# untitled.net
KiCad netlist of a schematic drawn in EAGLE
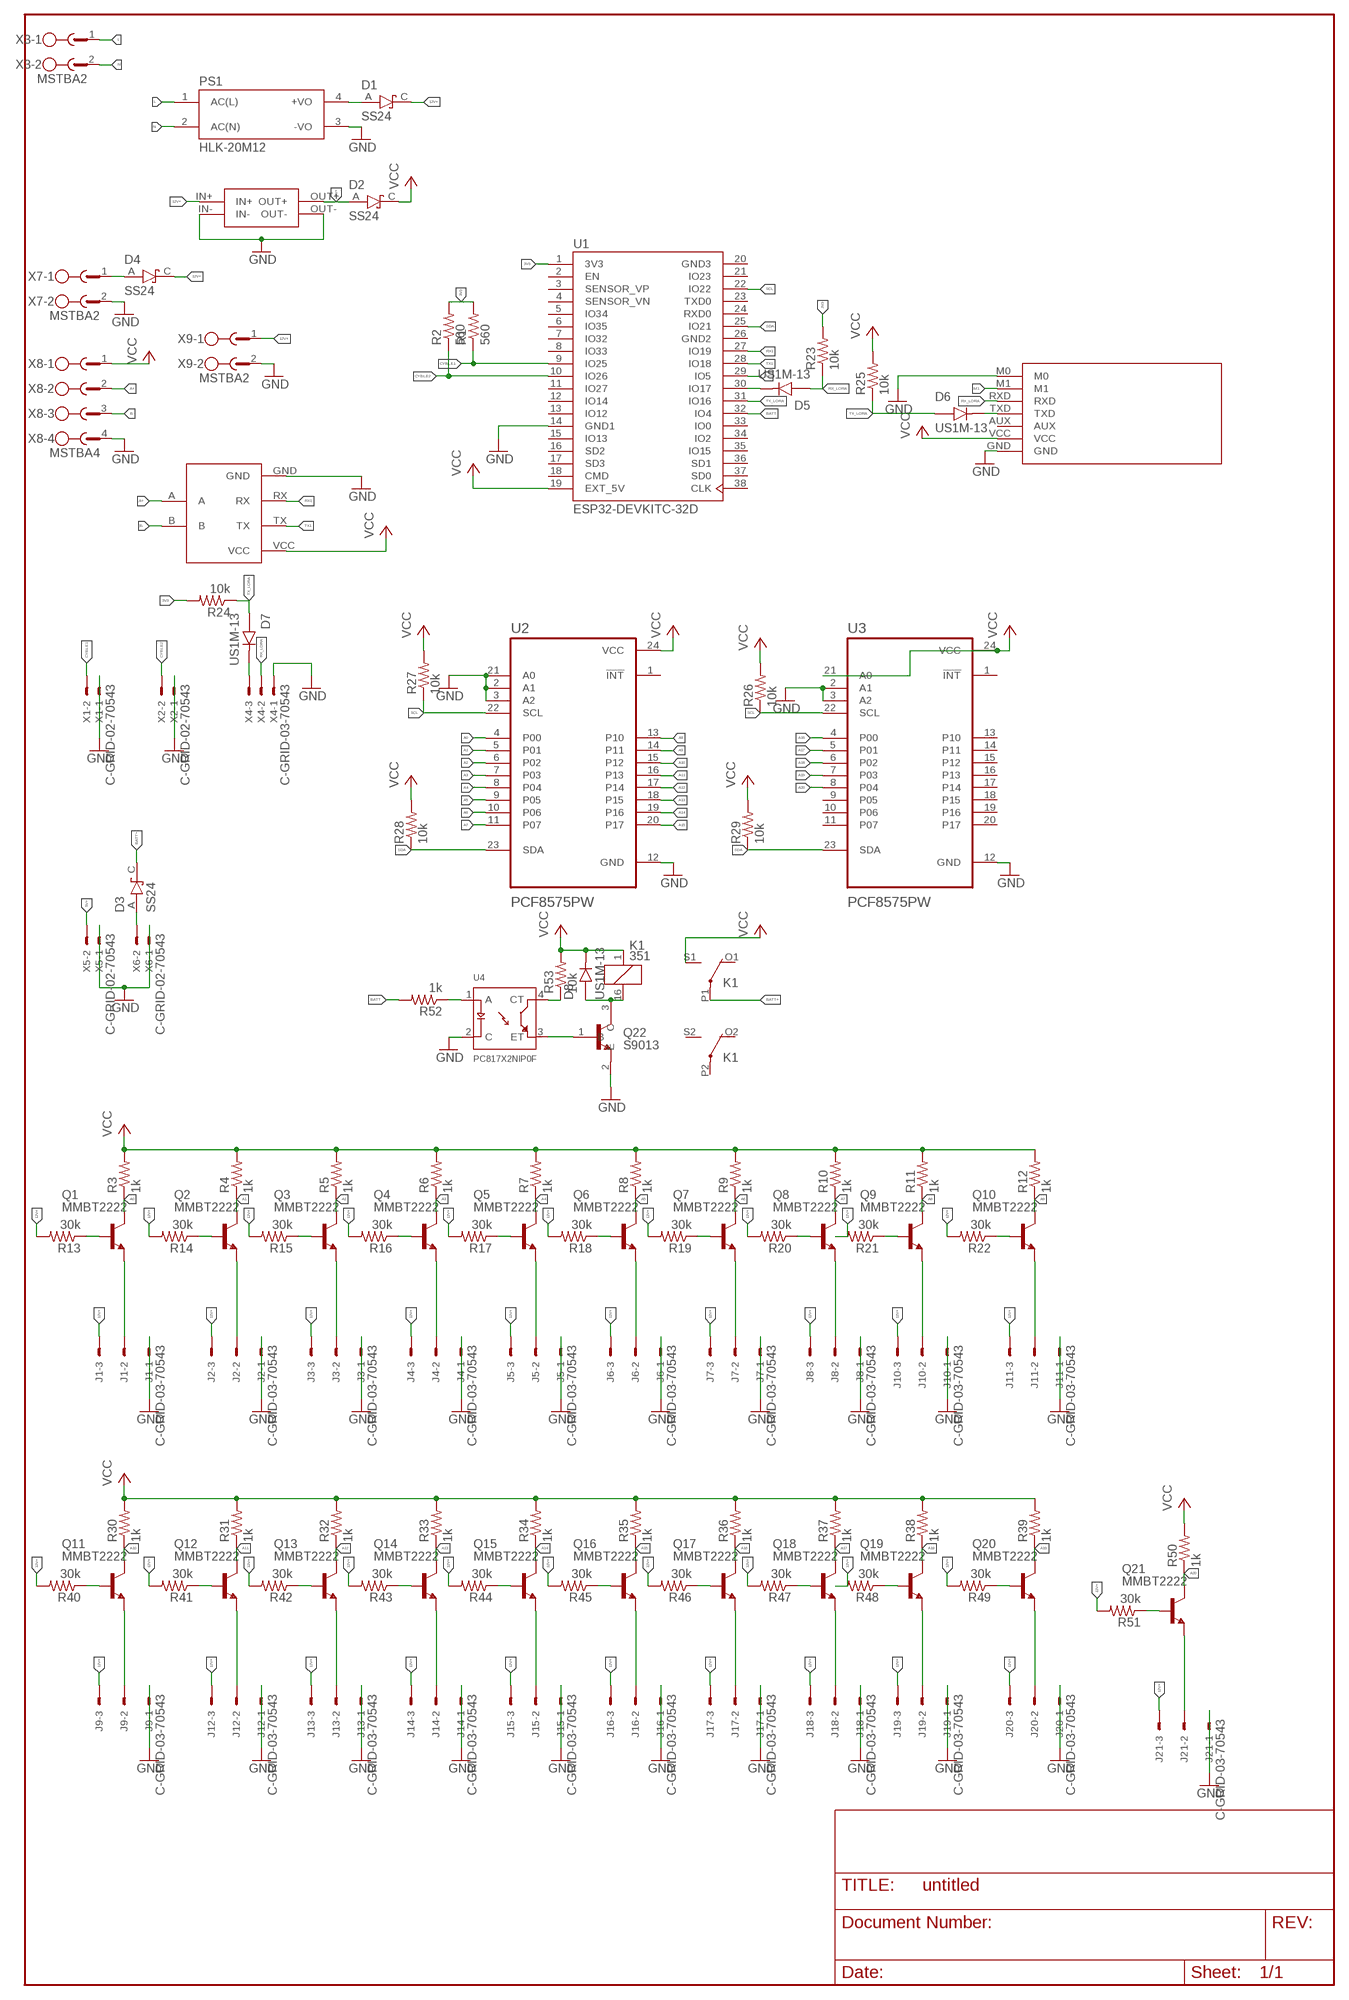
[diagram p0: schematic, sheet 1]

(export (version "E")
  (design (tool "Eeschema 10.0.6"))
  (components
    (comp (ref "D1")
      (value "SS24")
      (footprint "eagle-import:DIOM5336X265N")
      (fields (field (name "MF") "ON Semiconductor"))
      (libsource (lib "eagle-import") (part "SS24"))
    )
    (comp (ref "D2")
      (value "SS24")
      (footprint "eagle-import:DIOM5336X265N")
      (fields (field (name "MF") "ON Semiconductor"))
      (libsource (lib "eagle-import") (part "SS24"))
    )
    (comp (ref "D3")
      (value "SS24")
      (footprint "eagle-import:DIOM5336X265N")
      (fields (field (name "MF") "ON Semiconductor"))
      (libsource (lib "eagle-import") (part "SS24"))
    )
    (comp (ref "D4")
      (value "SS24")
      (footprint "eagle-import:DIOM5336X265N")
      (fields (field (name "MF") "ON Semiconductor"))
      (libsource (lib "eagle-import") (part "SS24"))
    )
    (comp (ref "D5")
      (value "US1M-13")
      (footprint "eagle-import:DIOM5226X240N")
      (fields (field (name "MF") "Diodes Incorporated"))
      (libsource (lib "eagle-import") (part "US1M-13"))
    )
    (comp (ref "D6")
      (value "US1M-13")
      (footprint "eagle-import:DIOM5226X240N")
      (fields (field (name "MF") "Diodes Incorporated"))
      (libsource (lib "eagle-import") (part "US1M-13"))
    )
    (comp (ref "D7")
      (value "US1M-13")
      (footprint "eagle-import:DIOM5226X240N")
      (fields (field (name "MF") "Diodes Incorporated"))
      (libsource (lib "eagle-import") (part "US1M-13"))
    )
    (comp (ref "D8")
      (value "US1M-13")
      (footprint "eagle-import:DIOM5226X240N")
      (fields (field (name "MF") "Diodes Incorporated"))
      (libsource (lib "eagle-import") (part "US1M-13"))
    )
    (comp (ref "EBYTEE220-900T22D1")
      (value "EBYTEE220-900T22D")
      (footprint "eagle-import:EBYTEE220-900T22D")
      (libsource (lib "eagle-import") (part "EBYTEE220-900T22D"))
    )
    (comp (ref "J1")
      (value "C-GRID-03-70543")
      (footprint "eagle-import:70543-03")
      (fields (field (name "MF") "MOLEX"))
      (libsource (lib "eagle-import") (part "C-GRID-03-70543"))
    )
    (comp (ref "J2")
      (value "C-GRID-03-70543")
      (footprint "eagle-import:70543-03")
      (fields (field (name "MF") "MOLEX"))
      (libsource (lib "eagle-import") (part "C-GRID-03-70543"))
    )
    (comp (ref "J3")
      (value "C-GRID-03-70543")
      (footprint "eagle-import:70543-03")
      (fields (field (name "MF") "MOLEX"))
      (libsource (lib "eagle-import") (part "C-GRID-03-70543"))
    )
    (comp (ref "J4")
      (value "C-GRID-03-70543")
      (footprint "eagle-import:70543-03")
      (fields (field (name "MF") "MOLEX"))
      (libsource (lib "eagle-import") (part "C-GRID-03-70543"))
    )
    (comp (ref "J5")
      (value "C-GRID-03-70543")
      (footprint "eagle-import:70543-03")
      (fields (field (name "MF") "MOLEX"))
      (libsource (lib "eagle-import") (part "C-GRID-03-70543"))
    )
    (comp (ref "J6")
      (value "C-GRID-03-70543")
      (footprint "eagle-import:70543-03")
      (fields (field (name "MF") "MOLEX"))
      (libsource (lib "eagle-import") (part "C-GRID-03-70543"))
    )
    (comp (ref "J7")
      (value "C-GRID-03-70543")
      (footprint "eagle-import:70543-03")
      (fields (field (name "MF") "MOLEX"))
      (libsource (lib "eagle-import") (part "C-GRID-03-70543"))
    )
    (comp (ref "J8")
      (value "C-GRID-03-70543")
      (footprint "eagle-import:70543-03")
      (fields (field (name "MF") "MOLEX"))
      (libsource (lib "eagle-import") (part "C-GRID-03-70543"))
    )
    (comp (ref "J9")
      (value "C-GRID-03-70543")
      (footprint "eagle-import:70543-03")
      (fields (field (name "MF") "MOLEX"))
      (libsource (lib "eagle-import") (part "C-GRID-03-70543"))
    )
    (comp (ref "J10")
      (value "C-GRID-03-70543")
      (footprint "eagle-import:70543-03")
      (fields (field (name "MF") "MOLEX"))
      (libsource (lib "eagle-import") (part "C-GRID-03-70543"))
    )
    (comp (ref "J11")
      (value "C-GRID-03-70543")
      (footprint "eagle-import:70543-03")
      (fields (field (name "MF") "MOLEX"))
      (libsource (lib "eagle-import") (part "C-GRID-03-70543"))
    )
    (comp (ref "J12")
      (value "C-GRID-03-70543")
      (footprint "eagle-import:70543-03")
      (fields (field (name "MF") "MOLEX"))
      (libsource (lib "eagle-import") (part "C-GRID-03-70543"))
    )
    (comp (ref "J13")
      (value "C-GRID-03-70543")
      (footprint "eagle-import:70543-03")
      (fields (field (name "MF") "MOLEX"))
      (libsource (lib "eagle-import") (part "C-GRID-03-70543"))
    )
    (comp (ref "J14")
      (value "C-GRID-03-70543")
      (footprint "eagle-import:70543-03")
      (fields (field (name "MF") "MOLEX"))
      (libsource (lib "eagle-import") (part "C-GRID-03-70543"))
    )
    (comp (ref "J15")
      (value "C-GRID-03-70543")
      (footprint "eagle-import:70543-03")
      (fields (field (name "MF") "MOLEX"))
      (libsource (lib "eagle-import") (part "C-GRID-03-70543"))
    )
    (comp (ref "J16")
      (value "C-GRID-03-70543")
      (footprint "eagle-import:70543-03")
      (fields (field (name "MF") "MOLEX"))
      (libsource (lib "eagle-import") (part "C-GRID-03-70543"))
    )
    (comp (ref "J17")
      (value "C-GRID-03-70543")
      (footprint "eagle-import:70543-03")
      (fields (field (name "MF") "MOLEX"))
      (libsource (lib "eagle-import") (part "C-GRID-03-70543"))
    )
    (comp (ref "J18")
      (value "C-GRID-03-70543")
      (footprint "eagle-import:70543-03")
      (fields (field (name "MF") "MOLEX"))
      (libsource (lib "eagle-import") (part "C-GRID-03-70543"))
    )
    (comp (ref "J19")
      (value "C-GRID-03-70543")
      (footprint "eagle-import:70543-03")
      (fields (field (name "MF") "MOLEX"))
      (libsource (lib "eagle-import") (part "C-GRID-03-70543"))
    )
    (comp (ref "J20")
      (value "C-GRID-03-70543")
      (footprint "eagle-import:70543-03")
      (fields (field (name "MF") "MOLEX"))
      (libsource (lib "eagle-import") (part "C-GRID-03-70543"))
    )
    (comp (ref "J21")
      (value "C-GRID-03-70543")
      (footprint "eagle-import:70543-03")
      (fields (field (name "MF") "MOLEX"))
      (libsource (lib "eagle-import") (part "C-GRID-03-70543"))
    )
    (comp (ref "K1")
      (value "351")
      (footprint "eagle-import:351")
      (libsource (lib "eagle-import") (part "351"))
    )
    (comp (ref "MINI1")
      (value "MINI560")
      (footprint "eagle-import:MINI560")
      (libsource (lib "eagle-import") (part "MINI560"))
    )
    (comp (ref "PS1")
      (value "HLK-20M12")
      (footprint "eagle-import:CONV_HLK-20M12")
      (fields (field (name "MF") "Hi-link"))
      (libsource (lib "eagle-import") (part "HLK-20M12"))
    )
    (comp (ref "Q1")
      (value "MMBT2222")
      (footprint "eagle-import:SOT23-BEC")
      (fields (field (name "MF") "ON Semiconductor"))
      (libsource (lib "eagle-import") (part "MMBT2222"))
    )
    (comp (ref "Q2")
      (value "MMBT2222")
      (footprint "eagle-import:SOT23-BEC")
      (fields (field (name "MF") "ON Semiconductor"))
      (libsource (lib "eagle-import") (part "MMBT2222"))
    )
    (comp (ref "Q3")
      (value "MMBT2222")
      (footprint "eagle-import:SOT23-BEC")
      (fields (field (name "MF") "ON Semiconductor"))
      (libsource (lib "eagle-import") (part "MMBT2222"))
    )
    (comp (ref "Q4")
      (value "MMBT2222")
      (footprint "eagle-import:SOT23-BEC")
      (fields (field (name "MF") "ON Semiconductor"))
      (libsource (lib "eagle-import") (part "MMBT2222"))
    )
    (comp (ref "Q5")
      (value "MMBT2222")
      (footprint "eagle-import:SOT23-BEC")
      (fields (field (name "MF") "ON Semiconductor"))
      (libsource (lib "eagle-import") (part "MMBT2222"))
    )
    (comp (ref "Q6")
      (value "MMBT2222")
      (footprint "eagle-import:SOT23-BEC")
      (fields (field (name "MF") "ON Semiconductor"))
      (libsource (lib "eagle-import") (part "MMBT2222"))
    )
    (comp (ref "Q7")
      (value "MMBT2222")
      (footprint "eagle-import:SOT23-BEC")
      (fields (field (name "MF") "ON Semiconductor"))
      (libsource (lib "eagle-import") (part "MMBT2222"))
    )
    (comp (ref "Q8")
      (value "MMBT2222")
      (footprint "eagle-import:SOT23-BEC")
      (fields (field (name "MF") "ON Semiconductor"))
      (libsource (lib "eagle-import") (part "MMBT2222"))
    )
    (comp (ref "Q9")
      (value "MMBT2222")
      (footprint "eagle-import:SOT23-BEC")
      (fields (field (name "MF") "ON Semiconductor"))
      (libsource (lib "eagle-import") (part "MMBT2222"))
    )
    (comp (ref "Q10")
      (value "MMBT2222")
      (footprint "eagle-import:SOT23-BEC")
      (fields (field (name "MF") "ON Semiconductor"))
      (libsource (lib "eagle-import") (part "MMBT2222"))
    )
    (comp (ref "Q11")
      (value "MMBT2222")
      (footprint "eagle-import:SOT23-BEC")
      (fields (field (name "MF") "ON Semiconductor"))
      (libsource (lib "eagle-import") (part "MMBT2222"))
    )
    (comp (ref "Q12")
      (value "MMBT2222")
      (footprint "eagle-import:SOT23-BEC")
      (fields (field (name "MF") "ON Semiconductor"))
      (libsource (lib "eagle-import") (part "MMBT2222"))
    )
    (comp (ref "Q13")
      (value "MMBT2222")
      (footprint "eagle-import:SOT23-BEC")
      (fields (field (name "MF") "ON Semiconductor"))
      (libsource (lib "eagle-import") (part "MMBT2222"))
    )
    (comp (ref "Q14")
      (value "MMBT2222")
      (footprint "eagle-import:SOT23-BEC")
      (fields (field (name "MF") "ON Semiconductor"))
      (libsource (lib "eagle-import") (part "MMBT2222"))
    )
    (comp (ref "Q15")
      (value "MMBT2222")
      (footprint "eagle-import:SOT23-BEC")
      (fields (field (name "MF") "ON Semiconductor"))
      (libsource (lib "eagle-import") (part "MMBT2222"))
    )
    (comp (ref "Q16")
      (value "MMBT2222")
      (footprint "eagle-import:SOT23-BEC")
      (fields (field (name "MF") "ON Semiconductor"))
      (libsource (lib "eagle-import") (part "MMBT2222"))
    )
    (comp (ref "Q17")
      (value "MMBT2222")
      (footprint "eagle-import:SOT23-BEC")
      (fields (field (name "MF") "ON Semiconductor"))
      (libsource (lib "eagle-import") (part "MMBT2222"))
    )
    (comp (ref "Q18")
      (value "MMBT2222")
      (footprint "eagle-import:SOT23-BEC")
      (fields (field (name "MF") "ON Semiconductor"))
      (libsource (lib "eagle-import") (part "MMBT2222"))
    )
    (comp (ref "Q19")
      (value "MMBT2222")
      (footprint "eagle-import:SOT23-BEC")
      (fields (field (name "MF") "ON Semiconductor"))
      (libsource (lib "eagle-import") (part "MMBT2222"))
    )
    (comp (ref "Q20")
      (value "MMBT2222")
      (footprint "eagle-import:SOT23-BEC")
      (fields (field (name "MF") "ON Semiconductor"))
      (libsource (lib "eagle-import") (part "MMBT2222"))
    )
    (comp (ref "Q21")
      (value "MMBT2222")
      (footprint "eagle-import:SOT23-BEC")
      (fields (field (name "MF") "ON Semiconductor"))
      (libsource (lib "eagle-import") (part "MMBT2222"))
    )
    (comp (ref "Q22")
      (value "S9013")
      (footprint "eagle-import:SOT95P240X120-3N")
      (fields (field (name "MF") "JCET"))
      (libsource (lib "eagle-import") (part "S9013"))
    )
    (comp (ref "R1")
      (value "560")
      (footprint "eagle-import:M0805")
      (libsource (lib "eagle-import") (part "R-US_M0805"))
    )
    (comp (ref "R2")
      (value "560")
      (footprint "eagle-import:M0805")
      (libsource (lib "eagle-import") (part "R-US_M0805"))
    )
    (comp (ref "R3")
      (value "1k")
      (footprint "eagle-import:M0805")
      (libsource (lib "eagle-import") (part "R-US_M0805"))
    )
    (comp (ref "R4")
      (value "1k")
      (footprint "eagle-import:M0805")
      (libsource (lib "eagle-import") (part "R-US_M0805"))
    )
    (comp (ref "R5")
      (value "1k")
      (footprint "eagle-import:M0805")
      (libsource (lib "eagle-import") (part "R-US_M0805"))
    )
    (comp (ref "R6")
      (value "1k")
      (footprint "eagle-import:M0805")
      (libsource (lib "eagle-import") (part "R-US_M0805"))
    )
    (comp (ref "R7")
      (value "1k")
      (footprint "eagle-import:M0805")
      (libsource (lib "eagle-import") (part "R-US_M0805"))
    )
    (comp (ref "R8")
      (value "1k")
      (footprint "eagle-import:M0805")
      (libsource (lib "eagle-import") (part "R-US_M0805"))
    )
    (comp (ref "R9")
      (value "1k")
      (footprint "eagle-import:M0805")
      (libsource (lib "eagle-import") (part "R-US_M0805"))
    )
    (comp (ref "R10")
      (value "1k")
      (footprint "eagle-import:M0805")
      (libsource (lib "eagle-import") (part "R-US_M0805"))
    )
    (comp (ref "R11")
      (value "1k")
      (footprint "eagle-import:M0805")
      (libsource (lib "eagle-import") (part "R-US_M0805"))
    )
    (comp (ref "R12")
      (value "1k")
      (footprint "eagle-import:M0805")
      (libsource (lib "eagle-import") (part "R-US_M0805"))
    )
    (comp (ref "R13")
      (value "30k")
      (footprint "eagle-import:M0805")
      (libsource (lib "eagle-import") (part "R-US_M0805"))
    )
    (comp (ref "R14")
      (value "30k")
      (footprint "eagle-import:M0805")
      (libsource (lib "eagle-import") (part "R-US_M0805"))
    )
    (comp (ref "R15")
      (value "30k")
      (footprint "eagle-import:M0805")
      (libsource (lib "eagle-import") (part "R-US_M0805"))
    )
    (comp (ref "R16")
      (value "30k")
      (footprint "eagle-import:M0805")
      (libsource (lib "eagle-import") (part "R-US_M0805"))
    )
    (comp (ref "R17")
      (value "30k")
      (footprint "eagle-import:M0805")
      (libsource (lib "eagle-import") (part "R-US_M0805"))
    )
    (comp (ref "R18")
      (value "30k")
      (footprint "eagle-import:M0805")
      (libsource (lib "eagle-import") (part "R-US_M0805"))
    )
    (comp (ref "R19")
      (value "30k")
      (footprint "eagle-import:M0805")
      (libsource (lib "eagle-import") (part "R-US_M0805"))
    )
    (comp (ref "R20")
      (value "30k")
      (footprint "eagle-import:M0805")
      (libsource (lib "eagle-import") (part "R-US_M0805"))
    )
    (comp (ref "R21")
      (value "30k")
      (footprint "eagle-import:M0805")
      (libsource (lib "eagle-import") (part "R-US_M0805"))
    )
    (comp (ref "R22")
      (value "30k")
      (footprint "eagle-import:M0805")
      (libsource (lib "eagle-import") (part "R-US_M0805"))
    )
    (comp (ref "R23")
      (value "10k")
      (footprint "eagle-import:M0805")
      (libsource (lib "eagle-import") (part "R-US_M0805"))
    )
    (comp (ref "R24")
      (value "10k")
      (footprint "eagle-import:M0805")
      (libsource (lib "eagle-import") (part "R-US_M0805"))
    )
    (comp (ref "R25")
      (value "10k")
      (footprint "eagle-import:M0805")
      (libsource (lib "eagle-import") (part "R-US_M0805"))
    )
    (comp (ref "R26")
      (value "10k")
      (footprint "eagle-import:M0805")
      (libsource (lib "eagle-import") (part "R-US_M0805"))
    )
    (comp (ref "R27")
      (value "10k")
      (footprint "eagle-import:M0805")
      (libsource (lib "eagle-import") (part "R-US_M0805"))
    )
    (comp (ref "R28")
      (value "10k")
      (footprint "eagle-import:M0805")
      (libsource (lib "eagle-import") (part "R-US_M0805"))
    )
    (comp (ref "R29")
      (value "10k")
      (footprint "eagle-import:M0805")
      (libsource (lib "eagle-import") (part "R-US_M0805"))
    )
    (comp (ref "R30")
      (value "1k")
      (footprint "eagle-import:M0805")
      (libsource (lib "eagle-import") (part "R-US_M0805"))
    )
    (comp (ref "R31")
      (value "1k")
      (footprint "eagle-import:M0805")
      (libsource (lib "eagle-import") (part "R-US_M0805"))
    )
    (comp (ref "R32")
      (value "1k")
      (footprint "eagle-import:M0805")
      (libsource (lib "eagle-import") (part "R-US_M0805"))
    )
    (comp (ref "R33")
      (value "1k")
      (footprint "eagle-import:M0805")
      (libsource (lib "eagle-import") (part "R-US_M0805"))
    )
    (comp (ref "R34")
      (value "1k")
      (footprint "eagle-import:M0805")
      (libsource (lib "eagle-import") (part "R-US_M0805"))
    )
    (comp (ref "R35")
      (value "1k")
      (footprint "eagle-import:M0805")
      (libsource (lib "eagle-import") (part "R-US_M0805"))
    )
    (comp (ref "R36")
      (value "1k")
      (footprint "eagle-import:M0805")
      (libsource (lib "eagle-import") (part "R-US_M0805"))
    )
    (comp (ref "R37")
      (value "1k")
      (footprint "eagle-import:M0805")
      (libsource (lib "eagle-import") (part "R-US_M0805"))
    )
    (comp (ref "R38")
      (value "1k")
      (footprint "eagle-import:M0805")
      (libsource (lib "eagle-import") (part "R-US_M0805"))
    )
    (comp (ref "R39")
      (value "1k")
      (footprint "eagle-import:M0805")
      (libsource (lib "eagle-import") (part "R-US_M0805"))
    )
    (comp (ref "R40")
      (value "30k")
      (footprint "eagle-import:M0805")
      (libsource (lib "eagle-import") (part "R-US_M0805"))
    )
    (comp (ref "R41")
      (value "30k")
      (footprint "eagle-import:M0805")
      (libsource (lib "eagle-import") (part "R-US_M0805"))
    )
    (comp (ref "R42")
      (value "30k")
      (footprint "eagle-import:M0805")
      (libsource (lib "eagle-import") (part "R-US_M0805"))
    )
    (comp (ref "R43")
      (value "30k")
      (footprint "eagle-import:M0805")
      (libsource (lib "eagle-import") (part "R-US_M0805"))
    )
    (comp (ref "R44")
      (value "30k")
      (footprint "eagle-import:M0805")
      (libsource (lib "eagle-import") (part "R-US_M0805"))
    )
    (comp (ref "R45")
      (value "30k")
      (footprint "eagle-import:M0805")
      (libsource (lib "eagle-import") (part "R-US_M0805"))
    )
    (comp (ref "R46")
      (value "30k")
      (footprint "eagle-import:M0805")
      (libsource (lib "eagle-import") (part "R-US_M0805"))
    )
    (comp (ref "R47")
      (value "30k")
      (footprint "eagle-import:M0805")
      (libsource (lib "eagle-import") (part "R-US_M0805"))
    )
    (comp (ref "R48")
      (value "30k")
      (footprint "eagle-import:M0805")
      (libsource (lib "eagle-import") (part "R-US_M0805"))
    )
    (comp (ref "R49")
      (value "30k")
      (footprint "eagle-import:M0805")
      (libsource (lib "eagle-import") (part "R-US_M0805"))
    )
    (comp (ref "R50")
      (value "1k")
      (footprint "eagle-import:M0805")
      (libsource (lib "eagle-import") (part "R-US_M0805"))
    )
    (comp (ref "R51")
      (value "30k")
      (footprint "eagle-import:M0805")
      (libsource (lib "eagle-import") (part "R-US_M0805"))
    )
    (comp (ref "R52")
      (value "1k")
      (footprint "eagle-import:M0805")
      (libsource (lib "eagle-import") (part "R-US_M0805"))
    )
    (comp (ref "R53")
      (value "10k")
      (footprint "eagle-import:M0805")
      (libsource (lib "eagle-import") (part "R-US_M0805"))
    )
    (comp (ref "TTL-RS1")
      (value "TTL-RS485")
      (footprint "eagle-import:TTL-RS485")
      (libsource (lib "eagle-import") (part "TTL-RS485"))
    )
    (comp (ref "U1")
      (value "ESP32-DEVKITC-32D")
      (footprint "eagle-import:MODULE_ESP32-DEVKITC-32D")
      (fields (field (name "MF") "Espressif Systems"))
      (libsource (lib "eagle-import") (part "ESP32-DEVKITC-32D"))
    )
    (comp (ref "U2")
      (value "PCF8575PW")
      (footprint "eagle-import:SOP65P640X120-24N")
      (fields (field (name "MF") "Texas Instruments"))
      (libsource (lib "eagle-import") (part "PCF8575PW"))
    )
    (comp (ref "U3")
      (value "PCF8575PW")
      (footprint "eagle-import:SOP65P640X120-24N")
      (fields (field (name "MF") "Texas Instruments"))
      (libsource (lib "eagle-import") (part "PCF8575PW"))
    )
    (comp (ref "U4")
      (value "PC817X2NIP0F")
      (footprint "eagle-import:SOT254P975X400-4N")
      (fields (field (name "MF") "Sharp Microelectronics"))
      (libsource (lib "eagle-import") (part "PC817X2NIP0F"))
    )
    (comp (ref "X1")
      (value "C-GRID-02-70543")
      (footprint "eagle-import:70543-02")
      (fields (field (name "MF") "MOLEX"))
      (libsource (lib "eagle-import") (part "C-GRID-02-70543"))
    )
    (comp (ref "X2")
      (value "C-GRID-02-70543")
      (footprint "eagle-import:70543-02")
      (fields (field (name "MF") "MOLEX"))
      (libsource (lib "eagle-import") (part "C-GRID-02-70543"))
    )
    (comp (ref "X3")
      (value "MSTBA2")
      (footprint "eagle-import:MSTBA2")
      (fields (field (name "MF") "FARNELL") (field (name "MPN") "1757242"))
      (libsource (lib "eagle-import") (part "MSTBA2"))
    )
    (comp (ref "X4")
      (value "C-GRID-03-70543")
      (footprint "eagle-import:70543-03")
      (fields (field (name "MF") "MOLEX"))
      (libsource (lib "eagle-import") (part "C-GRID-03-70543"))
    )
    (comp (ref "X5")
      (value "C-GRID-02-70543")
      (footprint "eagle-import:70543-02")
      (fields (field (name "MF") "MOLEX"))
      (libsource (lib "eagle-import") (part "C-GRID-02-70543"))
    )
    (comp (ref "X6")
      (value "C-GRID-02-70543")
      (footprint "eagle-import:70543-02")
      (fields (field (name "MF") "MOLEX"))
      (libsource (lib "eagle-import") (part "C-GRID-02-70543"))
    )
    (comp (ref "X7")
      (value "MSTBA2")
      (footprint "eagle-import:MSTBA2")
      (fields (field (name "MF") "FARNELL") (field (name "MPN") "1757242"))
      (libsource (lib "eagle-import") (part "MSTBA2"))
    )
    (comp (ref "X8")
      (value "MSTBA4")
      (footprint "eagle-import:MSTBA4")
      (fields (field (name "MF") "FARNELL") (field (name "MPN") "1757268"))
      (libsource (lib "eagle-import") (part "MSTBA4"))
    )
    (comp (ref "X9")
      (value "MSTBA2")
      (footprint "eagle-import:MSTBA2")
      (fields (field (name "MF") "FARNELL") (field (name "MPN") "1757242"))
      (libsource (lib "eagle-import") (part "MSTBA2"))
    )
  )
  (nets
    (net (code "1") (name "/GND2") (class "Default")
      (node (ref "U1") (pin "26") (pinfunction "GND2_26") (pintype "power_in"))
    )
    (net (code "2") (name "/GND3") (class "Default")
      (node (ref "U1") (pin "20") (pinfunction "GND3_20") (pintype "power_in"))
    )
    (net (code "3") (name "3V3") (class "Default")
      (node (ref "R1") (pin "2") (pinfunction "2_2") (pintype "passive"))
      (node (ref "R2") (pin "2") (pinfunction "2_2") (pintype "passive"))
      (node (ref "R23") (pin "2") (pinfunction "2_2") (pintype "passive"))
      (node (ref "R24") (pin "2") (pinfunction "2_2") (pintype "passive"))
      (node (ref "U1") (pin "1") (pinfunction "3V3_1") (pintype "power_in"))
    )
    (net (code "4") (name "5V+") (class "Default")
      (node (ref "D2") (pin "A") (pinfunction "A_A") (pintype "passive"))
      (node (ref "MINI1") (pin "OUT+") (pinfunction "OUT+_OUT+") (pintype "bidirectional"))
      (node (ref "X5") (pin "2") (pinfunction "S_2") (pintype "passive"))
    )
    (net (code "5") (name "12V+") (class "Default")
      (node (ref "D1") (pin "C") (pinfunction "K_C") (pintype "passive"))
      (node (ref "D4") (pin "C") (pinfunction "K_C") (pintype "passive"))
      (node (ref "J1") (pin "3") (pinfunction "S_3") (pintype "passive"))
      (node (ref "J10") (pin "3") (pinfunction "S_3") (pintype "passive"))
      (node (ref "J11") (pin "3") (pinfunction "S_3") (pintype "passive"))
      (node (ref "J12") (pin "3") (pinfunction "S_3") (pintype "passive"))
      (node (ref "J13") (pin "3") (pinfunction "S_3") (pintype "passive"))
      (node (ref "J14") (pin "3") (pinfunction "S_3") (pintype "passive"))
      (node (ref "J15") (pin "3") (pinfunction "S_3") (pintype "passive"))
      (node (ref "J16") (pin "3") (pinfunction "S_3") (pintype "passive"))
      (node (ref "J17") (pin "3") (pinfunction "S_3") (pintype "passive"))
      (node (ref "J18") (pin "3") (pinfunction "S_3") (pintype "passive"))
      (node (ref "J19") (pin "3") (pinfunction "S_3") (pintype "passive"))
      (node (ref "J2") (pin "3") (pinfunction "S_3") (pintype "passive"))
      (node (ref "J20") (pin "3") (pinfunction "S_3") (pintype "passive"))
      (node (ref "J21") (pin "3") (pinfunction "S_3") (pintype "passive"))
      (node (ref "J3") (pin "3") (pinfunction "S_3") (pintype "passive"))
      (node (ref "J4") (pin "3") (pinfunction "S_3") (pintype "passive"))
      (node (ref "J5") (pin "3") (pinfunction "S_3") (pintype "passive"))
      (node (ref "J6") (pin "3") (pinfunction "S_3") (pintype "passive"))
      (node (ref "J7") (pin "3") (pinfunction "S_3") (pintype "passive"))
      (node (ref "J8") (pin "3") (pinfunction "S_3") (pintype "passive"))
      (node (ref "J9") (pin "3") (pinfunction "S_3") (pintype "passive"))
      (node (ref "MINI1") (pin "IN+") (pinfunction "IN+_IN+") (pintype "bidirectional"))
      (node (ref "R13") (pin "2") (pinfunction "2_2") (pintype "passive"))
      (node (ref "R14") (pin "2") (pinfunction "2_2") (pintype "passive"))
      (node (ref "R15") (pin "2") (pinfunction "2_2") (pintype "passive"))
      (node (ref "R16") (pin "2") (pinfunction "2_2") (pintype "passive"))
      (node (ref "R17") (pin "2") (pinfunction "2_2") (pintype "passive"))
      (node (ref "R18") (pin "2") (pinfunction "2_2") (pintype "passive"))
      (node (ref "R19") (pin "2") (pinfunction "2_2") (pintype "passive"))
      (node (ref "R20") (pin "2") (pinfunction "2_2") (pintype "passive"))
      (node (ref "R21") (pin "2") (pinfunction "2_2") (pintype "passive"))
      (node (ref "R22") (pin "2") (pinfunction "2_2") (pintype "passive"))
      (node (ref "R40") (pin "2") (pinfunction "2_2") (pintype "passive"))
      (node (ref "R41") (pin "2") (pinfunction "2_2") (pintype "passive"))
      (node (ref "R42") (pin "2") (pinfunction "2_2") (pintype "passive"))
      (node (ref "R43") (pin "2") (pinfunction "2_2") (pintype "passive"))
      (node (ref "R44") (pin "2") (pinfunction "2_2") (pintype "passive"))
      (node (ref "R45") (pin "2") (pinfunction "2_2") (pintype "passive"))
      (node (ref "R46") (pin "2") (pinfunction "2_2") (pintype "passive"))
      (node (ref "R47") (pin "2") (pinfunction "2_2") (pintype "passive"))
      (node (ref "R48") (pin "2") (pinfunction "2_2") (pintype "passive"))
      (node (ref "R49") (pin "2") (pinfunction "2_2") (pintype "passive"))
      (node (ref "R51") (pin "2") (pinfunction "2_2") (pintype "passive"))
      (node (ref "X9") (pin "1") (pinfunction "1_1") (pintype "passive"))
    )
    (net (code "6") (name "A+") (class "Default")
      (node (ref "TTL-RS1") (pin "A") (pinfunction "A_A") (pintype "bidirectional"))
      (node (ref "X8") (pin "2") (pinfunction "1_2") (pintype "passive"))
    )
    (net (code "7") (name "A0") (class "Default")
      (node (ref "Q1") (pin "C") (pinfunction "C_C") (pintype "passive"))
      (node (ref "R3") (pin "1") (pinfunction "1_1") (pintype "passive"))
      (node (ref "U2") (pin "4") (pinfunction "P00_4") (pintype "bidirectional"))
    )
    (net (code "8") (name "A1") (class "Default")
      (node (ref "Q2") (pin "C") (pinfunction "C_C") (pintype "passive"))
      (node (ref "R4") (pin "1") (pinfunction "1_1") (pintype "passive"))
      (node (ref "U2") (pin "5") (pinfunction "P01_5") (pintype "bidirectional"))
    )
    (net (code "9") (name "A2") (class "Default")
      (node (ref "Q3") (pin "C") (pinfunction "C_C") (pintype "passive"))
      (node (ref "R5") (pin "1") (pinfunction "1_1") (pintype "passive"))
      (node (ref "U2") (pin "6") (pinfunction "P02_6") (pintype "bidirectional"))
    )
    (net (code "10") (name "A3") (class "Default")
      (node (ref "Q4") (pin "C") (pinfunction "C_C") (pintype "passive"))
      (node (ref "R6") (pin "1") (pinfunction "1_1") (pintype "passive"))
      (node (ref "U2") (pin "7") (pinfunction "P03_7") (pintype "bidirectional"))
    )
    (net (code "11") (name "A4") (class "Default")
      (node (ref "Q5") (pin "C") (pinfunction "C_C") (pintype "passive"))
      (node (ref "R7") (pin "1") (pinfunction "1_1") (pintype "passive"))
      (node (ref "U2") (pin "8") (pinfunction "P04_8") (pintype "bidirectional"))
    )
    (net (code "12") (name "A5") (class "Default")
      (node (ref "Q6") (pin "C") (pinfunction "C_C") (pintype "passive"))
      (node (ref "R8") (pin "1") (pinfunction "1_1") (pintype "passive"))
      (node (ref "U2") (pin "9") (pinfunction "P05_9") (pintype "bidirectional"))
    )
    (net (code "13") (name "A6") (class "Default")
      (node (ref "Q7") (pin "C") (pinfunction "C_C") (pintype "passive"))
      (node (ref "R9") (pin "1") (pinfunction "1_1") (pintype "passive"))
      (node (ref "U2") (pin "10") (pinfunction "P06_10") (pintype "bidirectional"))
    )
    (net (code "14") (name "A7") (class "Default")
      (node (ref "Q8") (pin "C") (pinfunction "C_C") (pintype "passive"))
      (node (ref "R10") (pin "1") (pinfunction "1_1") (pintype "passive"))
      (node (ref "U2") (pin "11") (pinfunction "P07_11") (pintype "bidirectional"))
    )
    (net (code "15") (name "A8") (class "Default")
      (node (ref "Q9") (pin "C") (pinfunction "C_C") (pintype "passive"))
      (node (ref "R11") (pin "1") (pinfunction "1_1") (pintype "passive"))
      (node (ref "U2") (pin "13") (pinfunction "P10_13") (pintype "bidirectional"))
    )
    (net (code "16") (name "A9") (class "Default")
      (node (ref "Q10") (pin "C") (pinfunction "C_C") (pintype "passive"))
      (node (ref "R12") (pin "1") (pinfunction "1_1") (pintype "passive"))
      (node (ref "U2") (pin "14") (pinfunction "P11_14") (pintype "bidirectional"))
    )
    (net (code "17") (name "A10") (class "Default")
      (node (ref "Q11") (pin "C") (pinfunction "C_C") (pintype "passive"))
      (node (ref "R30") (pin "1") (pinfunction "1_1") (pintype "passive"))
      (node (ref "U2") (pin "15") (pinfunction "P12_15") (pintype "bidirectional"))
    )
    (net (code "18") (name "A11") (class "Default")
      (node (ref "Q12") (pin "C") (pinfunction "C_C") (pintype "passive"))
      (node (ref "R31") (pin "1") (pinfunction "1_1") (pintype "passive"))
      (node (ref "U2") (pin "16") (pinfunction "P13_16") (pintype "bidirectional"))
    )
    (net (code "19") (name "A12") (class "Default")
      (node (ref "Q13") (pin "C") (pinfunction "C_C") (pintype "passive"))
      (node (ref "R32") (pin "1") (pinfunction "1_1") (pintype "passive"))
      (node (ref "U2") (pin "17") (pinfunction "P14_17") (pintype "bidirectional"))
    )
    (net (code "20") (name "A13") (class "Default")
      (node (ref "Q14") (pin "C") (pinfunction "C_C") (pintype "passive"))
      (node (ref "R33") (pin "1") (pinfunction "1_1") (pintype "passive"))
      (node (ref "U2") (pin "18") (pinfunction "P15_18") (pintype "bidirectional"))
    )
    (net (code "21") (name "A14") (class "Default")
      (node (ref "Q15") (pin "C") (pinfunction "C_C") (pintype "passive"))
      (node (ref "R34") (pin "1") (pinfunction "1_1") (pintype "passive"))
      (node (ref "U2") (pin "19") (pinfunction "P16_19") (pintype "bidirectional"))
    )
    (net (code "22") (name "A15") (class "Default")
      (node (ref "Q16") (pin "C") (pinfunction "C_C") (pintype "passive"))
      (node (ref "R35") (pin "1") (pinfunction "1_1") (pintype "passive"))
      (node (ref "U2") (pin "20") (pinfunction "P17_20") (pintype "bidirectional"))
    )
    (net (code "23") (name "A16") (class "Default")
      (node (ref "Q17") (pin "C") (pinfunction "C_C") (pintype "passive"))
      (node (ref "R36") (pin "1") (pinfunction "1_1") (pintype "passive"))
      (node (ref "U3") (pin "4") (pinfunction "P00_4") (pintype "bidirectional"))
    )
    (net (code "24") (name "A17") (class "Default")
      (node (ref "Q18") (pin "C") (pinfunction "C_C") (pintype "passive"))
      (node (ref "R37") (pin "1") (pinfunction "1_1") (pintype "passive"))
      (node (ref "U3") (pin "5") (pinfunction "P01_5") (pintype "bidirectional"))
    )
    (net (code "25") (name "A18") (class "Default")
      (node (ref "Q19") (pin "C") (pinfunction "C_C") (pintype "passive"))
      (node (ref "R38") (pin "1") (pinfunction "1_1") (pintype "passive"))
      (node (ref "U3") (pin "6") (pinfunction "P02_6") (pintype "bidirectional"))
    )
    (net (code "26") (name "A19") (class "Default")
      (node (ref "Q20") (pin "C") (pinfunction "C_C") (pintype "passive"))
      (node (ref "R39") (pin "1") (pinfunction "1_1") (pintype "passive"))
      (node (ref "U3") (pin "7") (pinfunction "P03_7") (pintype "bidirectional"))
    )
    (net (code "27") (name "A20") (class "Default")
      (node (ref "Q21") (pin "C") (pinfunction "C_C") (pintype "passive"))
      (node (ref "R50") (pin "1") (pinfunction "1_1") (pintype "passive"))
      (node (ref "U3") (pin "8") (pinfunction "P04_8") (pintype "bidirectional"))
    )
    (net (code "28") (name "B-") (class "Default")
      (node (ref "TTL-RS1") (pin "B") (pinfunction "B_B") (pintype "bidirectional"))
      (node (ref "X8") (pin "3") (pinfunction "1_3") (pintype "passive"))
    )
    (net (code "29") (name "BATT") (class "Default")
      (node (ref "R52") (pin "2") (pinfunction "2_2") (pintype "passive"))
      (node (ref "U1") (pin "32") (pinfunction "IO4_32") (pintype "bidirectional"))
    )
    (net (code "30") (name "BATT+") (class "Default")
      (node (ref "D3") (pin "C") (pinfunction "K_C") (pintype "passive"))
      (node (ref "K1") (pin "P1") (pinfunction "P_P1") (pintype "passive"))
    )
    (net (code "31") (name "CYBLE1") (class "Default")
      (node (ref "R1") (pin "1") (pinfunction "1_1") (pintype "passive"))
      (node (ref "U1") (pin "9") (pinfunction "IO25_9") (pintype "bidirectional"))
      (node (ref "X1") (pin "2") (pinfunction "S_2") (pintype "passive"))
    )
    (net (code "32") (name "CYBLE2") (class "Default")
      (node (ref "R2") (pin "1") (pinfunction "1_1") (pintype "passive"))
      (node (ref "U1") (pin "10") (pinfunction "IO26_10") (pintype "bidirectional"))
      (node (ref "X2") (pin "2") (pinfunction "S_2") (pintype "passive"))
    )
    (net (code "33") (name "GND") (class "Default")
      (node (ref "EBYTEE220-900T22D1") (pin "GND") (pinfunction "GND_GND") (pintype "bidirectional"))
      (node (ref "EBYTEE220-900T22D1") (pin "M0") (pinfunction "M0_M0") (pintype "bidirectional"))
      (node (ref "J1") (pin "1") (pinfunction "S_1") (pintype "passive"))
      (node (ref "J10") (pin "1") (pinfunction "S_1") (pintype "passive"))
      (node (ref "J11") (pin "1") (pinfunction "S_1") (pintype "passive"))
      (node (ref "J12") (pin "1") (pinfunction "S_1") (pintype "passive"))
      (node (ref "J13") (pin "1") (pinfunction "S_1") (pintype "passive"))
      (node (ref "J14") (pin "1") (pinfunction "S_1") (pintype "passive"))
      (node (ref "J15") (pin "1") (pinfunction "S_1") (pintype "passive"))
      (node (ref "J16") (pin "1") (pinfunction "S_1") (pintype "passive"))
      (node (ref "J17") (pin "1") (pinfunction "S_1") (pintype "passive"))
      (node (ref "J18") (pin "1") (pinfunction "S_1") (pintype "passive"))
      (node (ref "J19") (pin "1") (pinfunction "S_1") (pintype "passive"))
      (node (ref "J2") (pin "1") (pinfunction "S_1") (pintype "passive"))
      (node (ref "J20") (pin "1") (pinfunction "S_1") (pintype "passive"))
      (node (ref "J21") (pin "1") (pinfunction "S_1") (pintype "passive"))
      (node (ref "J3") (pin "1") (pinfunction "S_1") (pintype "passive"))
      (node (ref "J4") (pin "1") (pinfunction "S_1") (pintype "passive"))
      (node (ref "J5") (pin "1") (pinfunction "S_1") (pintype "passive"))
      (node (ref "J6") (pin "1") (pinfunction "S_1") (pintype "passive"))
      (node (ref "J7") (pin "1") (pinfunction "S_1") (pintype "passive"))
      (node (ref "J8") (pin "1") (pinfunction "S_1") (pintype "passive"))
      (node (ref "J9") (pin "1") (pinfunction "S_1") (pintype "passive"))
      (node (ref "MINI1") (pin "IN-") (pinfunction "IN-_IN-") (pintype "bidirectional"))
      (node (ref "MINI1") (pin "OUT-") (pinfunction "OUT-_OUT-") (pintype "bidirectional"))
      (node (ref "PS1") (pin "3") (pinfunction "-VO_3") (pintype "output"))
      (node (ref "Q22") (pin "2") (pinfunction "E_2") (pintype "passive"))
      (node (ref "TTL-RS1") (pin "GND") (pinfunction "GND_GND") (pintype "bidirectional"))
      (node (ref "U1") (pin "14") (pinfunction "GND1_14") (pintype "power_in"))
      (node (ref "U2") (pin "12") (pinfunction "GND_12") (pintype "power_in"))
      (node (ref "U2") (pin "2") (pinfunction "A1_2") (pintype "input"))
      (node (ref "U2") (pin "21") (pinfunction "A0_21") (pintype "input"))
      (node (ref "U2") (pin "3") (pinfunction "A2_3") (pintype "input"))
      (node (ref "U3") (pin "12") (pinfunction "GND_12") (pintype "power_in"))
      (node (ref "U3") (pin "2") (pinfunction "A1_2") (pintype "input"))
      (node (ref "U3") (pin "3") (pinfunction "A2_3") (pintype "input"))
      (node (ref "U4") (pin "2") (pinfunction "C_2") (pintype "passive"))
      (node (ref "X1") (pin "1") (pinfunction "S_1") (pintype "passive"))
      (node (ref "X2") (pin "1") (pinfunction "S_1") (pintype "passive"))
      (node (ref "X4") (pin "1") (pinfunction "S_1") (pintype "passive"))
      (node (ref "X5") (pin "1") (pinfunction "S_1") (pintype "passive"))
      (node (ref "X6") (pin "1") (pinfunction "S_1") (pintype "passive"))
      (node (ref "X7") (pin "2") (pinfunction "1_2") (pintype "passive"))
      (node (ref "X8") (pin "4") (pinfunction "1_4") (pintype "passive"))
      (node (ref "X9") (pin "2") (pinfunction "1_2") (pintype "passive"))
    )
    (net (code "34") (name "L") (class "Default")
      (node (ref "PS1") (pin "1") (pinfunction "AC(L)_1") (pintype "input"))
      (node (ref "X3") (pin "1") (pinfunction "1_1") (pintype "passive"))
    )
    (net (code "35") (name "M1") (class "Default")
      (node (ref "EBYTEE220-900T22D1") (pin "M1") (pinfunction "M1_M1") (pintype "bidirectional"))
      (node (ref "U1") (pin "29") (pinfunction "IO5_29") (pintype "bidirectional"))
    )
    (net (code "36") (name "N") (class "Default")
      (node (ref "PS1") (pin "2") (pinfunction "AC(N)_2") (pintype "input"))
      (node (ref "X3") (pin "2") (pinfunction "1_2") (pintype "passive"))
    )
    (net (code "37") (name "Net-(D4-PadA)") (class "Default")
      (node (ref "D4") (pin "A") (pinfunction "A_A") (pintype "passive"))
      (node (ref "X7") (pin "1") (pinfunction "1_1") (pintype "passive"))
    )
    (net (code "38") (name "Net-(D5-K)") (class "Default")
      (node (ref "D5") (pin "C") (pinfunction "K_C") (pintype "passive"))
      (node (ref "U1") (pin "30") (pinfunction "IO17_30") (pintype "bidirectional"))
    )
    (net (code "39") (name "Net-(D6-K)") (class "Default")
      (node (ref "D6") (pin "C") (pinfunction "K_C") (pintype "passive"))
      (node (ref "EBYTEE220-900T22D1") (pin "TXD") (pinfunction "TXD_TXD") (pintype "bidirectional"))
    )
    (net (code "40") (name "Net-(D7-K)") (class "Default")
      (node (ref "D7") (pin "C") (pinfunction "K_C") (pintype "passive"))
      (node (ref "X4") (pin "3") (pinfunction "S_3") (pintype "passive"))
    )
    (net (code "41") (name "Net-(J1B-S)") (class "Default")
      (node (ref "J1") (pin "2") (pinfunction "S_2") (pintype "passive"))
      (node (ref "Q1") (pin "E") (pinfunction "E_E") (pintype "passive"))
    )
    (net (code "42") (name "Net-(J2B-S)") (class "Default")
      (node (ref "J2") (pin "2") (pinfunction "S_2") (pintype "passive"))
      (node (ref "Q2") (pin "E") (pinfunction "E_E") (pintype "passive"))
    )
    (net (code "43") (name "Net-(J3B-S)") (class "Default")
      (node (ref "J3") (pin "2") (pinfunction "S_2") (pintype "passive"))
      (node (ref "Q3") (pin "E") (pinfunction "E_E") (pintype "passive"))
    )
    (net (code "44") (name "Net-(J4B-S)") (class "Default")
      (node (ref "J4") (pin "2") (pinfunction "S_2") (pintype "passive"))
      (node (ref "Q4") (pin "E") (pinfunction "E_E") (pintype "passive"))
    )
    (net (code "45") (name "Net-(J5B-S)") (class "Default")
      (node (ref "J5") (pin "2") (pinfunction "S_2") (pintype "passive"))
      (node (ref "Q5") (pin "E") (pinfunction "E_E") (pintype "passive"))
    )
    (net (code "46") (name "Net-(J6B-S)") (class "Default")
      (node (ref "J6") (pin "2") (pinfunction "S_2") (pintype "passive"))
      (node (ref "Q6") (pin "E") (pinfunction "E_E") (pintype "passive"))
    )
    (net (code "47") (name "Net-(J7B-S)") (class "Default")
      (node (ref "J7") (pin "2") (pinfunction "S_2") (pintype "passive"))
      (node (ref "Q7") (pin "E") (pinfunction "E_E") (pintype "passive"))
    )
    (net (code "48") (name "Net-(J8B-S)") (class "Default")
      (node (ref "J8") (pin "2") (pinfunction "S_2") (pintype "passive"))
      (node (ref "Q8") (pin "E") (pinfunction "E_E") (pintype "passive"))
    )
    (net (code "49") (name "Net-(J9B-S)") (class "Default")
      (node (ref "J9") (pin "2") (pinfunction "S_2") (pintype "passive"))
      (node (ref "Q11") (pin "E") (pinfunction "E_E") (pintype "passive"))
    )
    (net (code "50") (name "Net-(J10B-S)") (class "Default")
      (node (ref "J10") (pin "2") (pinfunction "S_2") (pintype "passive"))
      (node (ref "Q9") (pin "E") (pinfunction "E_E") (pintype "passive"))
    )
    (net (code "51") (name "Net-(J11B-S)") (class "Default")
      (node (ref "J11") (pin "2") (pinfunction "S_2") (pintype "passive"))
      (node (ref "Q10") (pin "E") (pinfunction "E_E") (pintype "passive"))
    )
    (net (code "52") (name "Net-(J12B-S)") (class "Default")
      (node (ref "J12") (pin "2") (pinfunction "S_2") (pintype "passive"))
      (node (ref "Q12") (pin "E") (pinfunction "E_E") (pintype "passive"))
    )
    (net (code "53") (name "Net-(J13B-S)") (class "Default")
      (node (ref "J13") (pin "2") (pinfunction "S_2") (pintype "passive"))
      (node (ref "Q13") (pin "E") (pinfunction "E_E") (pintype "passive"))
    )
    (net (code "54") (name "Net-(J14B-S)") (class "Default")
      (node (ref "J14") (pin "2") (pinfunction "S_2") (pintype "passive"))
      (node (ref "Q14") (pin "E") (pinfunction "E_E") (pintype "passive"))
    )
    (net (code "55") (name "Net-(J15B-S)") (class "Default")
      (node (ref "J15") (pin "2") (pinfunction "S_2") (pintype "passive"))
      (node (ref "Q15") (pin "E") (pinfunction "E_E") (pintype "passive"))
    )
    (net (code "56") (name "Net-(J16B-S)") (class "Default")
      (node (ref "J16") (pin "2") (pinfunction "S_2") (pintype "passive"))
      (node (ref "Q16") (pin "E") (pinfunction "E_E") (pintype "passive"))
    )
    (net (code "57") (name "Net-(J17B-S)") (class "Default")
      (node (ref "J17") (pin "2") (pinfunction "S_2") (pintype "passive"))
      (node (ref "Q17") (pin "E") (pinfunction "E_E") (pintype "passive"))
    )
    (net (code "58") (name "Net-(J18B-S)") (class "Default")
      (node (ref "J18") (pin "2") (pinfunction "S_2") (pintype "passive"))
      (node (ref "Q18") (pin "E") (pinfunction "E_E") (pintype "passive"))
    )
    (net (code "59") (name "Net-(J19B-S)") (class "Default")
      (node (ref "J19") (pin "2") (pinfunction "S_2") (pintype "passive"))
      (node (ref "Q19") (pin "E") (pinfunction "E_E") (pintype "passive"))
    )
    (net (code "60") (name "Net-(J20B-S)") (class "Default")
      (node (ref "J20") (pin "2") (pinfunction "S_2") (pintype "passive"))
      (node (ref "Q20") (pin "E") (pinfunction "E_E") (pintype "passive"))
    )
    (net (code "61") (name "Net-(J21B-S)") (class "Default")
      (node (ref "J21") (pin "2") (pinfunction "S_2") (pintype "passive"))
      (node (ref "Q21") (pin "E") (pinfunction "E_E") (pintype "passive"))
    )
    (net (code "62") (name "Net-(K1A-2)") (class "Default")
      (node (ref "D8") (pin "A") (pinfunction "A_A") (pintype "passive"))
      (node (ref "K1") (pin "16") (pinfunction "2_16") (pintype "passive"))
      (node (ref "Q22") (pin "3") (pinfunction "C_3") (pintype "passive"))
    )
    (net (code "63") (name "Net-(PS1-+VO)") (class "Default")
      (node (ref "D1") (pin "A") (pinfunction "A_A") (pintype "passive"))
      (node (ref "PS1") (pin "4") (pinfunction "+VO_4") (pintype "output"))
    )
    (net (code "64") (name "Net-(Q1-PadB)") (class "Default")
      (node (ref "Q1") (pin "B") (pinfunction "B_B") (pintype "passive"))
      (node (ref "R13") (pin "1") (pinfunction "1_1") (pintype "passive"))
    )
    (net (code "65") (name "Net-(Q2-PadB)") (class "Default")
      (node (ref "Q2") (pin "B") (pinfunction "B_B") (pintype "passive"))
      (node (ref "R14") (pin "1") (pinfunction "1_1") (pintype "passive"))
    )
    (net (code "66") (name "Net-(Q3-PadB)") (class "Default")
      (node (ref "Q3") (pin "B") (pinfunction "B_B") (pintype "passive"))
      (node (ref "R15") (pin "1") (pinfunction "1_1") (pintype "passive"))
    )
    (net (code "67") (name "Net-(Q4-PadB)") (class "Default")
      (node (ref "Q4") (pin "B") (pinfunction "B_B") (pintype "passive"))
      (node (ref "R16") (pin "1") (pinfunction "1_1") (pintype "passive"))
    )
    (net (code "68") (name "Net-(Q5-PadB)") (class "Default")
      (node (ref "Q5") (pin "B") (pinfunction "B_B") (pintype "passive"))
      (node (ref "R17") (pin "1") (pinfunction "1_1") (pintype "passive"))
    )
    (net (code "69") (name "Net-(Q6-PadB)") (class "Default")
      (node (ref "Q6") (pin "B") (pinfunction "B_B") (pintype "passive"))
      (node (ref "R18") (pin "1") (pinfunction "1_1") (pintype "passive"))
    )
    (net (code "70") (name "Net-(Q7-PadB)") (class "Default")
      (node (ref "Q7") (pin "B") (pinfunction "B_B") (pintype "passive"))
      (node (ref "R19") (pin "1") (pinfunction "1_1") (pintype "passive"))
    )
    (net (code "71") (name "Net-(Q8-PadB)") (class "Default")
      (node (ref "Q8") (pin "B") (pinfunction "B_B") (pintype "passive"))
      (node (ref "R20") (pin "1") (pinfunction "1_1") (pintype "passive"))
    )
    (net (code "72") (name "Net-(Q9-PadB)") (class "Default")
      (node (ref "Q9") (pin "B") (pinfunction "B_B") (pintype "passive"))
      (node (ref "R21") (pin "1") (pinfunction "1_1") (pintype "passive"))
    )
    (net (code "73") (name "Net-(Q10-PadB)") (class "Default")
      (node (ref "Q10") (pin "B") (pinfunction "B_B") (pintype "passive"))
      (node (ref "R22") (pin "1") (pinfunction "1_1") (pintype "passive"))
    )
    (net (code "74") (name "Net-(Q11-PadB)") (class "Default")
      (node (ref "Q11") (pin "B") (pinfunction "B_B") (pintype "passive"))
      (node (ref "R40") (pin "1") (pinfunction "1_1") (pintype "passive"))
    )
    (net (code "75") (name "Net-(Q12-PadB)") (class "Default")
      (node (ref "Q12") (pin "B") (pinfunction "B_B") (pintype "passive"))
      (node (ref "R41") (pin "1") (pinfunction "1_1") (pintype "passive"))
    )
    (net (code "76") (name "Net-(Q13-PadB)") (class "Default")
      (node (ref "Q13") (pin "B") (pinfunction "B_B") (pintype "passive"))
      (node (ref "R42") (pin "1") (pinfunction "1_1") (pintype "passive"))
    )
    (net (code "77") (name "Net-(Q14-PadB)") (class "Default")
      (node (ref "Q14") (pin "B") (pinfunction "B_B") (pintype "passive"))
      (node (ref "R43") (pin "1") (pinfunction "1_1") (pintype "passive"))
    )
    (net (code "78") (name "Net-(Q15-PadB)") (class "Default")
      (node (ref "Q15") (pin "B") (pinfunction "B_B") (pintype "passive"))
      (node (ref "R44") (pin "1") (pinfunction "1_1") (pintype "passive"))
    )
    (net (code "79") (name "Net-(Q16-PadB)") (class "Default")
      (node (ref "Q16") (pin "B") (pinfunction "B_B") (pintype "passive"))
      (node (ref "R45") (pin "1") (pinfunction "1_1") (pintype "passive"))
    )
    (net (code "80") (name "Net-(Q17-PadB)") (class "Default")
      (node (ref "Q17") (pin "B") (pinfunction "B_B") (pintype "passive"))
      (node (ref "R46") (pin "1") (pinfunction "1_1") (pintype "passive"))
    )
    (net (code "81") (name "Net-(Q18-PadB)") (class "Default")
      (node (ref "Q18") (pin "B") (pinfunction "B_B") (pintype "passive"))
      (node (ref "R47") (pin "1") (pinfunction "1_1") (pintype "passive"))
    )
    (net (code "82") (name "Net-(Q19-PadB)") (class "Default")
      (node (ref "Q19") (pin "B") (pinfunction "B_B") (pintype "passive"))
      (node (ref "R48") (pin "1") (pinfunction "1_1") (pintype "passive"))
    )
    (net (code "83") (name "Net-(Q20-PadB)") (class "Default")
      (node (ref "Q20") (pin "B") (pinfunction "B_B") (pintype "passive"))
      (node (ref "R49") (pin "1") (pinfunction "1_1") (pintype "passive"))
    )
    (net (code "84") (name "Net-(Q21-PadB)") (class "Default")
      (node (ref "Q21") (pin "B") (pinfunction "B_B") (pintype "passive"))
      (node (ref "R51") (pin "1") (pinfunction "1_1") (pintype "passive"))
    )
    (net (code "85") (name "Net-(Q22-B)") (class "Default")
      (node (ref "Q22") (pin "1") (pinfunction "B_1") (pintype "passive"))
      (node (ref "U4") (pin "3") (pinfunction "ET_3") (pintype "passive"))
    )
    (net (code "86") (name "Net-(U4-A)") (class "Default")
      (node (ref "R52") (pin "1") (pinfunction "1_1") (pintype "passive"))
      (node (ref "U4") (pin "1") (pinfunction "A_1") (pintype "passive"))
    )
    (net (code "87") (name "Net-(U4-CT)") (class "Default")
      (node (ref "R53") (pin "1") (pinfunction "1_1") (pintype "passive"))
      (node (ref "U4") (pin "4") (pinfunction "CT_4") (pintype "passive"))
    )
    (net (code "88") (name "Net-(X6B-S)") (class "Default")
      (node (ref "D3") (pin "A") (pinfunction "A_A") (pintype "passive"))
      (node (ref "X6") (pin "2") (pinfunction "S_2") (pintype "passive"))
    )
    (net (code "89") (name "RX1") (class "Default")
      (node (ref "TTL-RS1") (pin "RX") (pinfunction "RX_RX") (pintype "bidirectional"))
      (node (ref "U1") (pin "27") (pinfunction "IO19_27") (pintype "bidirectional"))
    )
    (net (code "90") (name "RX_LORA") (class "Default")
      (node (ref "D5") (pin "A") (pinfunction "A_A") (pintype "passive"))
      (node (ref "EBYTEE220-900T22D1") (pin "RXD") (pinfunction "RXD_RXD") (pintype "bidirectional"))
      (node (ref "R23") (pin "1") (pinfunction "1_1") (pintype "passive"))
      (node (ref "X4") (pin "2") (pinfunction "S_2") (pintype "passive"))
    )
    (net (code "91") (name "SCL") (class "Default")
      (node (ref "R26") (pin "1") (pinfunction "1_1") (pintype "passive"))
      (node (ref "R27") (pin "1") (pinfunction "1_1") (pintype "passive"))
      (node (ref "U1") (pin "22") (pinfunction "IO22_22") (pintype "bidirectional"))
      (node (ref "U2") (pin "22") (pinfunction "SCL_22") (pintype "input"))
      (node (ref "U3") (pin "22") (pinfunction "SCL_22") (pintype "input"))
    )
    (net (code "92") (name "SDA") (class "Default")
      (node (ref "R28") (pin "1") (pinfunction "1_1") (pintype "passive"))
      (node (ref "R29") (pin "1") (pinfunction "1_1") (pintype "passive"))
      (node (ref "U1") (pin "25") (pinfunction "IO21_25") (pintype "bidirectional"))
      (node (ref "U2") (pin "23") (pinfunction "SDA_23") (pintype "bidirectional"))
      (node (ref "U3") (pin "23") (pinfunction "SDA_23") (pintype "bidirectional"))
    )
    (net (code "93") (name "TX1") (class "Default")
      (node (ref "TTL-RS1") (pin "TX") (pinfunction "TX_TX") (pintype "bidirectional"))
      (node (ref "U1") (pin "28") (pinfunction "IO18_28") (pintype "bidirectional"))
    )
    (net (code "94") (name "TX_LORA") (class "Default")
      (node (ref "D6") (pin "A") (pinfunction "A_A") (pintype "passive"))
      (node (ref "D7") (pin "A") (pinfunction "A_A") (pintype "passive"))
      (node (ref "R24") (pin "1") (pinfunction "1_1") (pintype "passive"))
      (node (ref "R25") (pin "1") (pinfunction "1_1") (pintype "passive"))
      (node (ref "U1") (pin "31") (pinfunction "IO16_31") (pintype "bidirectional"))
    )
    (net (code "95") (name "VCC") (class "Default")
      (node (ref "D2") (pin "C") (pinfunction "K_C") (pintype "passive"))
      (node (ref "D8") (pin "C") (pinfunction "K_C") (pintype "passive"))
      (node (ref "EBYTEE220-900T22D1") (pin "VCC") (pinfunction "VCC_VCC") (pintype "bidirectional"))
      (node (ref "K1") (pin "1") (pinfunction "1_1") (pintype "passive"))
      (node (ref "K1") (pin "S1") (pinfunction "S_S1") (pintype "passive"))
      (node (ref "R10") (pin "2") (pinfunction "2_2") (pintype "passive"))
      (node (ref "R11") (pin "2") (pinfunction "2_2") (pintype "passive"))
      (node (ref "R12") (pin "2") (pinfunction "2_2") (pintype "passive"))
      (node (ref "R25") (pin "2") (pinfunction "2_2") (pintype "passive"))
      (node (ref "R26") (pin "2") (pinfunction "2_2") (pintype "passive"))
      (node (ref "R27") (pin "2") (pinfunction "2_2") (pintype "passive"))
      (node (ref "R28") (pin "2") (pinfunction "2_2") (pintype "passive"))
      (node (ref "R29") (pin "2") (pinfunction "2_2") (pintype "passive"))
      (node (ref "R3") (pin "2") (pinfunction "2_2") (pintype "passive"))
      (node (ref "R30") (pin "2") (pinfunction "2_2") (pintype "passive"))
      (node (ref "R31") (pin "2") (pinfunction "2_2") (pintype "passive"))
      (node (ref "R32") (pin "2") (pinfunction "2_2") (pintype "passive"))
      (node (ref "R33") (pin "2") (pinfunction "2_2") (pintype "passive"))
      (node (ref "R34") (pin "2") (pinfunction "2_2") (pintype "passive"))
      (node (ref "R35") (pin "2") (pinfunction "2_2") (pintype "passive"))
      (node (ref "R36") (pin "2") (pinfunction "2_2") (pintype "passive"))
      (node (ref "R37") (pin "2") (pinfunction "2_2") (pintype "passive"))
      (node (ref "R38") (pin "2") (pinfunction "2_2") (pintype "passive"))
      (node (ref "R39") (pin "2") (pinfunction "2_2") (pintype "passive"))
      (node (ref "R4") (pin "2") (pinfunction "2_2") (pintype "passive"))
      (node (ref "R5") (pin "2") (pinfunction "2_2") (pintype "passive"))
      (node (ref "R50") (pin "2") (pinfunction "2_2") (pintype "passive"))
      (node (ref "R53") (pin "2") (pinfunction "2_2") (pintype "passive"))
      (node (ref "R6") (pin "2") (pinfunction "2_2") (pintype "passive"))
      (node (ref "R7") (pin "2") (pinfunction "2_2") (pintype "passive"))
      (node (ref "R8") (pin "2") (pinfunction "2_2") (pintype "passive"))
      (node (ref "R9") (pin "2") (pinfunction "2_2") (pintype "passive"))
      (node (ref "TTL-RS1") (pin "VCC") (pinfunction "VCC_VCC") (pintype "bidirectional"))
      (node (ref "U1") (pin "19") (pinfunction "EXT_5V_19") (pintype "power_in"))
      (node (ref "U2") (pin "24") (pinfunction "VCC_24") (pintype "power_in"))
      (node (ref "U3") (pin "21") (pinfunction "A0_21") (pintype "input"))
      (node (ref "U3") (pin "24") (pinfunction "VCC_24") (pintype "power_in"))
      (node (ref "X8") (pin "1") (pinfunction "1_1") (pintype "passive"))
    )
    (net (code "96") (name "unconnected-(EBYTEE220-900T22D1-PadAUX)") (class "Default")
      (node (ref "EBYTEE220-900T22D1") (pin "AUX") (pinfunction "AUX_AUX") (pintype "bidirectional"))
    )
    (net (code "97") (name "unconnected-(K1B-O-PadO1)") (class "Default")
      (node (ref "K1") (pin "O1") (pinfunction "O_O1") (pintype "passive"))
    )
    (net (code "98") (name "unconnected-(K1C-O-PadO2)") (class "Default")
      (node (ref "K1") (pin "O2") (pinfunction "O_O2") (pintype "passive"))
    )
    (net (code "99") (name "unconnected-(K1C-P-PadP2)") (class "Default")
      (node (ref "K1") (pin "P2") (pinfunction "P_P2") (pintype "passive"))
    )
    (net (code "100") (name "unconnected-(K1C-S-PadS2)") (class "Default")
      (node (ref "K1") (pin "S2") (pinfunction "S_S2") (pintype "passive"))
    )
    (net (code "101") (name "unconnected-(U1-CLK-Pad38)") (class "Default")
      (node (ref "U1") (pin "38") (pinfunction "CLK_38") (pintype "input"))
    )
    (net (code "102") (name "unconnected-(U1-CMD-Pad18)") (class "Default")
      (node (ref "U1") (pin "18") (pinfunction "CMD_18") (pintype "bidirectional"))
    )
    (net (code "103") (name "unconnected-(U1-EN-Pad2)") (class "Default")
      (node (ref "U1") (pin "2") (pinfunction "EN_2") (pintype "input"))
    )
    (net (code "104") (name "unconnected-(U1-IO0-Pad33)") (class "Default")
      (node (ref "U1") (pin "33") (pinfunction "IO0_33") (pintype "bidirectional"))
    )
    (net (code "105") (name "unconnected-(U1-IO2-Pad34)") (class "Default")
      (node (ref "U1") (pin "34") (pinfunction "IO2_34") (pintype "bidirectional"))
    )
    (net (code "106") (name "unconnected-(U1-IO12-Pad13)") (class "Default")
      (node (ref "U1") (pin "13") (pinfunction "IO12_13") (pintype "bidirectional"))
    )
    (net (code "107") (name "unconnected-(U1-IO13-Pad15)") (class "Default")
      (node (ref "U1") (pin "15") (pinfunction "IO13_15") (pintype "bidirectional"))
    )
    (net (code "108") (name "unconnected-(U1-IO14-Pad12)") (class "Default")
      (node (ref "U1") (pin "12") (pinfunction "IO14_12") (pintype "bidirectional"))
    )
    (net (code "109") (name "unconnected-(U1-IO15-Pad35)") (class "Default")
      (node (ref "U1") (pin "35") (pinfunction "IO15_35") (pintype "bidirectional"))
    )
    (net (code "110") (name "unconnected-(U1-IO23-Pad21)") (class "Default")
      (node (ref "U1") (pin "21") (pinfunction "IO23_21") (pintype "bidirectional"))
    )
    (net (code "111") (name "unconnected-(U1-IO27-Pad11)") (class "Default")
      (node (ref "U1") (pin "11") (pinfunction "IO27_11") (pintype "bidirectional"))
    )
    (net (code "112") (name "unconnected-(U1-IO32-Pad7)") (class "Default")
      (node (ref "U1") (pin "7") (pinfunction "IO32_7") (pintype "bidirectional"))
    )
    (net (code "113") (name "unconnected-(U1-IO33-Pad8)") (class "Default")
      (node (ref "U1") (pin "8") (pinfunction "IO33_8") (pintype "bidirectional"))
    )
    (net (code "114") (name "unconnected-(U1-IO34-Pad5)") (class "Default")
      (node (ref "U1") (pin "5") (pinfunction "IO34_5") (pintype "bidirectional"))
    )
    (net (code "115") (name "unconnected-(U1-IO35-Pad6)") (class "Default")
      (node (ref "U1") (pin "6") (pinfunction "IO35_6") (pintype "bidirectional"))
    )
    (net (code "116") (name "unconnected-(U1-RXD0-Pad24)") (class "Default")
      (node (ref "U1") (pin "24") (pinfunction "RXD0_24") (pintype "input"))
    )
    (net (code "117") (name "unconnected-(U1-SD0-Pad37)") (class "Default")
      (node (ref "U1") (pin "37") (pinfunction "SD0_37") (pintype "bidirectional"))
    )
    (net (code "118") (name "unconnected-(U1-SD1-Pad36)") (class "Default")
      (node (ref "U1") (pin "36") (pinfunction "SD1_36") (pintype "bidirectional"))
    )
    (net (code "119") (name "unconnected-(U1-SD2-Pad16)") (class "Default")
      (node (ref "U1") (pin "16") (pinfunction "SD2_16") (pintype "bidirectional"))
    )
    (net (code "120") (name "unconnected-(U1-SD3-Pad17)") (class "Default")
      (node (ref "U1") (pin "17") (pinfunction "SD3_17") (pintype "bidirectional"))
    )
    (net (code "121") (name "unconnected-(U1-SENSOR_VN-Pad4)") (class "Default")
      (node (ref "U1") (pin "4") (pinfunction "SENSOR_VN_4") (pintype "input"))
    )
    (net (code "122") (name "unconnected-(U1-SENSOR_VP-Pad3)") (class "Default")
      (node (ref "U1") (pin "3") (pinfunction "SENSOR_VP_3") (pintype "input"))
    )
    (net (code "123") (name "unconnected-(U1-TXD0-Pad23)") (class "Default")
      (node (ref "U1") (pin "23") (pinfunction "TXD0_23") (pintype "output"))
    )
    (net (code "124") (name "unconnected-(U2-~{INT}-Pad1)") (class "Default")
      (node (ref "U2") (pin "1") (pinfunction "~{INT}_1") (pintype "output"))
    )
    (net (code "125") (name "unconnected-(U3-P05-Pad9)") (class "Default")
      (node (ref "U3") (pin "9") (pinfunction "P05_9") (pintype "bidirectional"))
    )
    (net (code "126") (name "unconnected-(U3-P06-Pad10)") (class "Default")
      (node (ref "U3") (pin "10") (pinfunction "P06_10") (pintype "bidirectional"))
    )
    (net (code "127") (name "unconnected-(U3-P07-Pad11)") (class "Default")
      (node (ref "U3") (pin "11") (pinfunction "P07_11") (pintype "bidirectional"))
    )
    (net (code "128") (name "unconnected-(U3-P10-Pad13)") (class "Default")
      (node (ref "U3") (pin "13") (pinfunction "P10_13") (pintype "bidirectional"))
    )
    (net (code "129") (name "unconnected-(U3-P11-Pad14)") (class "Default")
      (node (ref "U3") (pin "14") (pinfunction "P11_14") (pintype "bidirectional"))
    )
    (net (code "130") (name "unconnected-(U3-P12-Pad15)") (class "Default")
      (node (ref "U3") (pin "15") (pinfunction "P12_15") (pintype "bidirectional"))
    )
    (net (code "131") (name "unconnected-(U3-P13-Pad16)") (class "Default")
      (node (ref "U3") (pin "16") (pinfunction "P13_16") (pintype "bidirectional"))
    )
    (net (code "132") (name "unconnected-(U3-P14-Pad17)") (class "Default")
      (node (ref "U3") (pin "17") (pinfunction "P14_17") (pintype "bidirectional"))
    )
    (net (code "133") (name "unconnected-(U3-P15-Pad18)") (class "Default")
      (node (ref "U3") (pin "18") (pinfunction "P15_18") (pintype "bidirectional"))
    )
    (net (code "134") (name "unconnected-(U3-P16-Pad19)") (class "Default")
      (node (ref "U3") (pin "19") (pinfunction "P16_19") (pintype "bidirectional"))
    )
    (net (code "135") (name "unconnected-(U3-P17-Pad20)") (class "Default")
      (node (ref "U3") (pin "20") (pinfunction "P17_20") (pintype "bidirectional"))
    )
    (net (code "136") (name "unconnected-(U3-~{INT}-Pad1)") (class "Default")
      (node (ref "U3") (pin "1") (pinfunction "~{INT}_1") (pintype "output"))
    )
  )
)
